# G431_Dev_V2.net
KiCad netlist of a schematic drawn in Altium Designer
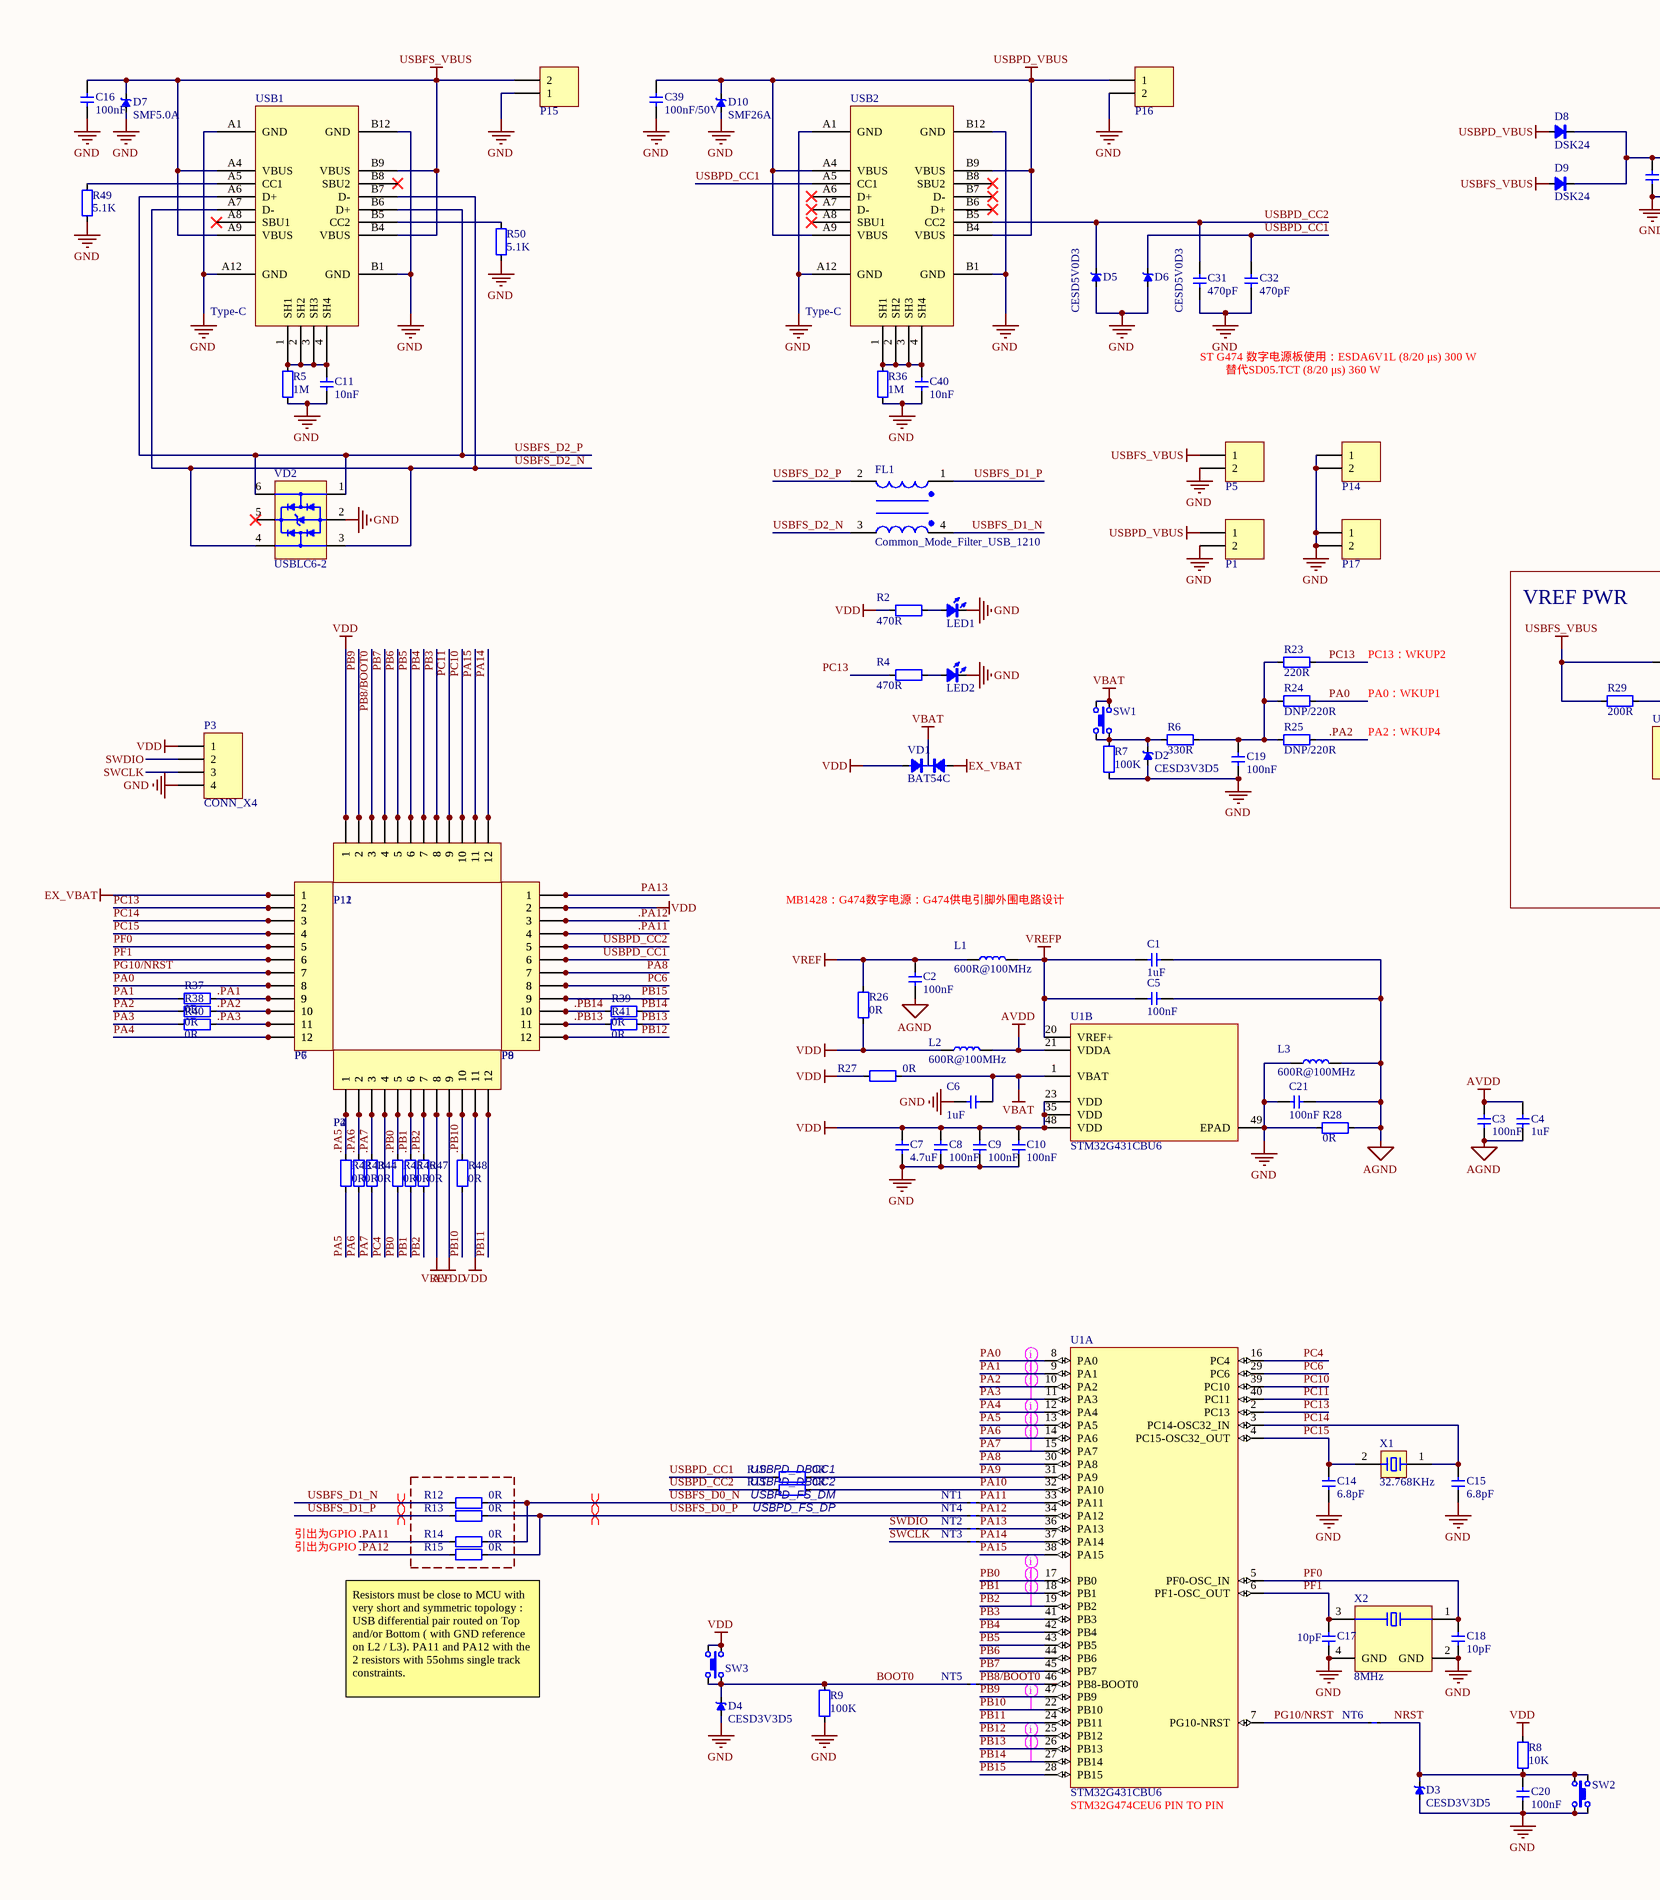
[diagram p0: G431_Dev_V2.SchDoc, left]
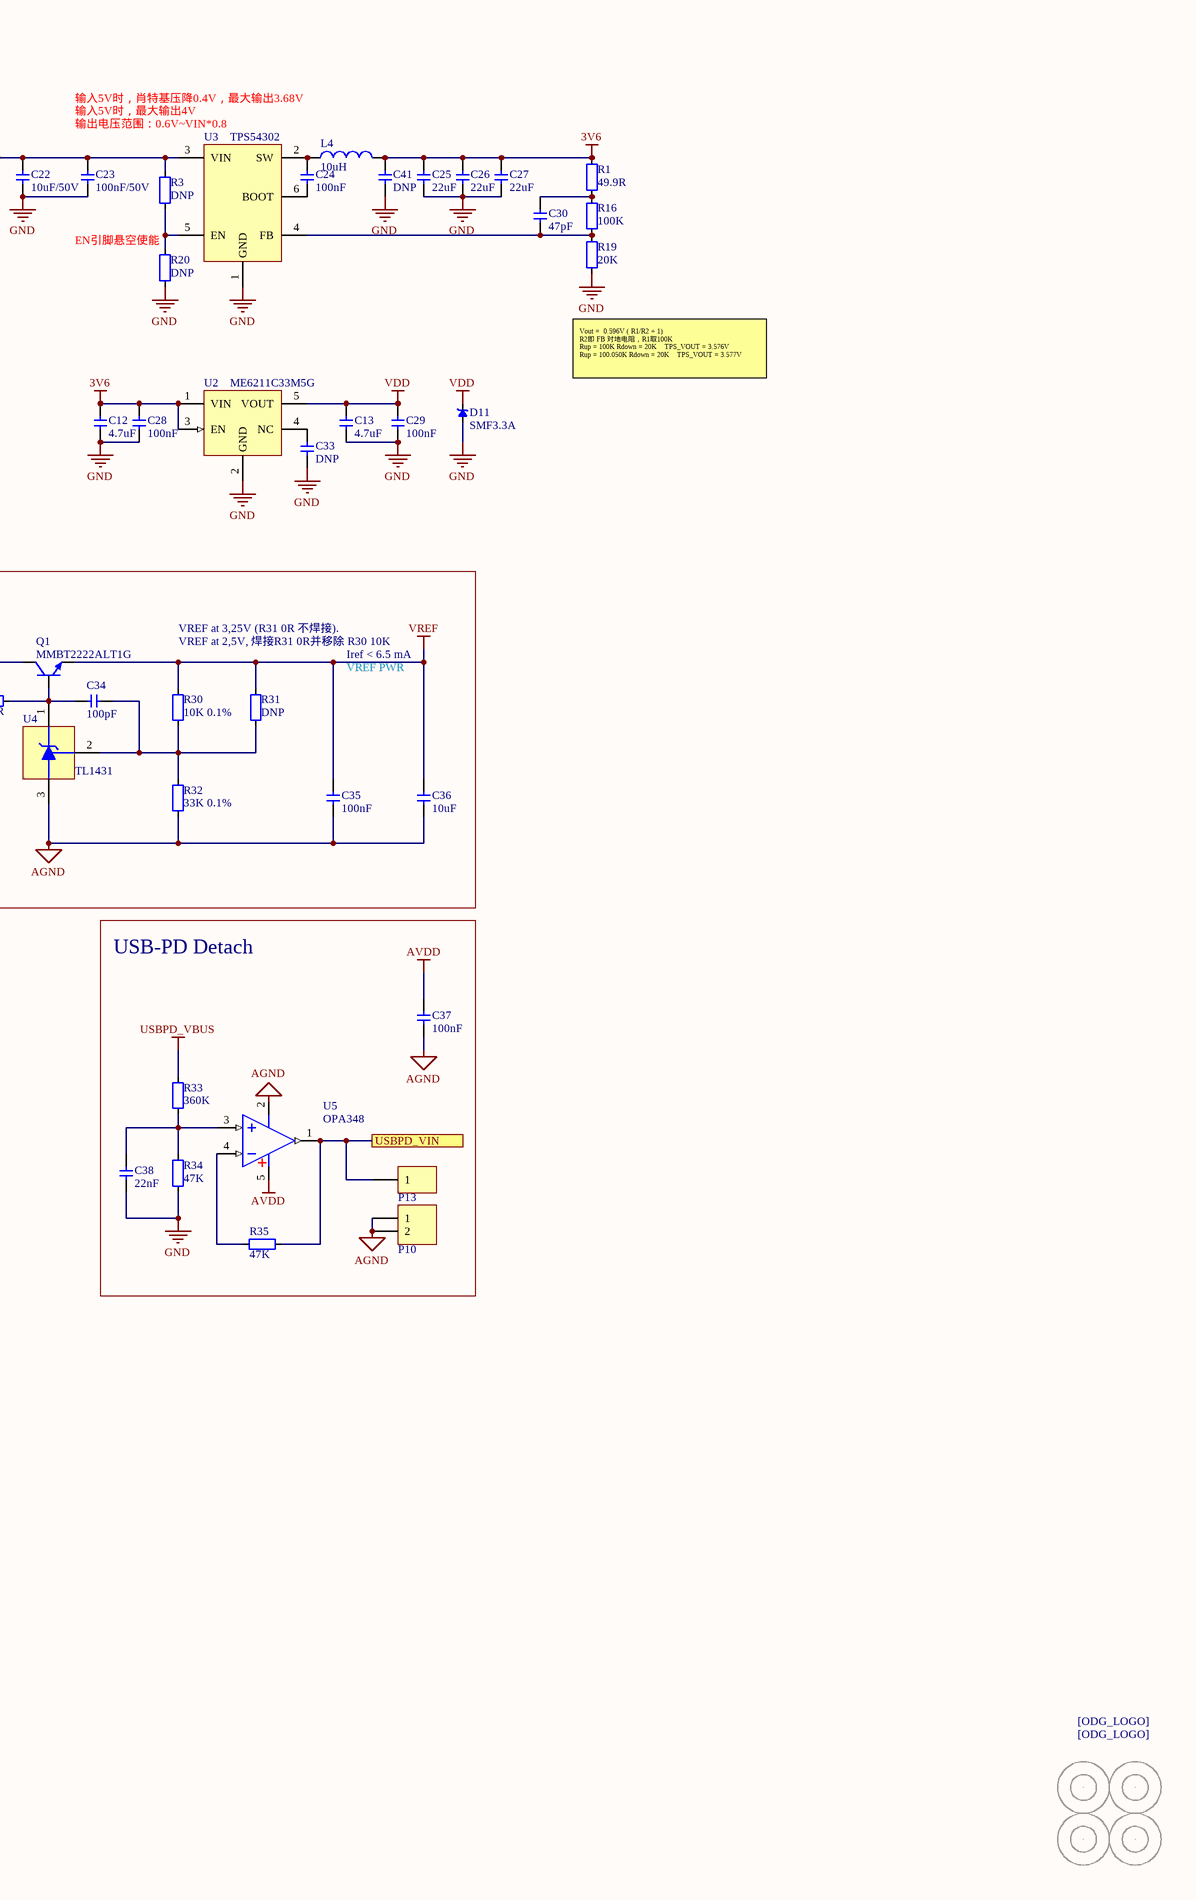
[diagram p1: G431_Dev_V2.SchDoc, right]

(export (version "E")
  (design (tool "Eeschema 10.0.6"))
  (components
    (comp (ref "*1")
      (value "ODG_LOGO")
      (footprint "ODG_LOGO")
      (libsource (lib "ODG_AD_Lib") (part "ODG_LOGO"))
    )
    (comp (ref "*2")
      (value "ODG_LOGO")
      (footprint "ODG_LOGO")
      (libsource (lib "ODG_AD_Lib") (part "ODG_LOGO"))
    )
    (comp (ref "C1")
      (value "1uF")
      (footprint "C0603")
      (description "Capacitor")
      (libsource (lib "ODG_AD_Lib") (part "CAP"))
    )
    (comp (ref "C2")
      (value "100nF")
      (footprint "C0402")
      (description "Capacitor")
      (libsource (lib "ODG_AD_Lib") (part "CAP"))
    )
    (comp (ref "C3")
      (value "100nF")
      (footprint "C0402")
      (description "Capacitor")
      (libsource (lib "ODG_AD_Lib") (part "CAP"))
    )
    (comp (ref "C4")
      (value "1uF")
      (footprint "C0603")
      (description "Capacitor")
      (libsource (lib "ODG_AD_Lib") (part "CAP"))
    )
    (comp (ref "C5")
      (value "100nF")
      (footprint "C0402")
      (description "Capacitor")
      (libsource (lib "ODG_AD_Lib") (part "CAP"))
    )
    (comp (ref "C6")
      (value "1uF")
      (footprint "C0603")
      (description "Capacitor")
      (libsource (lib "ODG_AD_Lib") (part "CAP"))
    )
    (comp (ref "C7")
      (value "4.7uF")
      (footprint "C0603")
      (description "Capacitor")
      (libsource (lib "ODG_AD_Lib") (part "CAP"))
    )
    (comp (ref "C8")
      (value "100nF")
      (footprint "C0402")
      (description "Capacitor")
      (libsource (lib "ODG_AD_Lib") (part "CAP"))
    )
    (comp (ref "C9")
      (value "100nF")
      (footprint "C0402")
      (description "Capacitor")
      (libsource (lib "ODG_AD_Lib") (part "CAP"))
    )
    (comp (ref "C10")
      (value "100nF")
      (footprint "C0402")
      (description "Capacitor")
      (libsource (lib "ODG_AD_Lib") (part "CAP"))
    )
    (comp (ref "C11")
      (value "10nF")
      (footprint "C0402")
      (description "Capacitor")
      (libsource (lib "ODG_AD_Lib") (part "CAP"))
    )
    (comp (ref "C12")
      (value "4.7uF")
      (footprint "C0603")
      (description "Capacitor")
      (libsource (lib "ODG_AD_Lib") (part "CAP"))
    )
    (comp (ref "C13")
      (value "4.7uF")
      (footprint "C0603")
      (description "Capacitor")
      (libsource (lib "ODG_AD_Lib") (part "CAP"))
    )
    (comp (ref "C14")
      (value "6.8pF")
      (footprint "C0402")
      (description "Capacitor")
      (libsource (lib "ODG_AD_Lib") (part "CAP"))
    )
    (comp (ref "C15")
      (value "6.8pF")
      (footprint "C0402")
      (description "Capacitor")
      (libsource (lib "ODG_AD_Lib") (part "CAP"))
    )
    (comp (ref "C16")
      (value "100nF")
      (footprint "C0402")
      (description "Capacitor")
      (libsource (lib "ODG_AD_Lib") (part "CAP"))
    )
    (comp (ref "C17")
      (value "10pF")
      (footprint "C0402")
      (description "Capacitor")
      (libsource (lib "ODG_AD_Lib") (part "CAP"))
    )
    (comp (ref "C18")
      (value "10pF")
      (footprint "C0402")
      (description "Capacitor")
      (libsource (lib "ODG_AD_Lib") (part "CAP"))
    )
    (comp (ref "C19")
      (value "100nF")
      (footprint "C0402")
      (description "Capacitor")
      (libsource (lib "ODG_AD_Lib") (part "CAP"))
    )
    (comp (ref "C20")
      (value "100nF")
      (footprint "C0402")
      (description "Capacitor")
      (libsource (lib "ODG_AD_Lib") (part "CAP"))
    )
    (comp (ref "C21")
      (value "100nF")
      (footprint "C0402")
      (description "Capacitor")
      (libsource (lib "ODG_AD_Lib") (part "CAP"))
    )
    (comp (ref "C22")
      (value "10uF/50V")
      (footprint "C1206")
      (description "Capacitor")
      (libsource (lib "ODG_AD_Lib") (part "CAP"))
    )
    (comp (ref "C23")
      (value "100nF/50V")
      (footprint "C0402")
      (description "Capacitor")
      (libsource (lib "ODG_AD_Lib") (part "CAP"))
    )
    (comp (ref "C24")
      (value "100nF")
      (footprint "C0402")
      (description "Capacitor")
      (libsource (lib "ODG_AD_Lib") (part "CAP"))
    )
    (comp (ref "C25")
      (value "22uF")
      (footprint "C0805")
      (description "Capacitor")
      (libsource (lib "ODG_AD_Lib") (part "CAP"))
    )
    (comp (ref "C26")
      (value "22uF")
      (footprint "C0805")
      (description "Capacitor")
      (libsource (lib "ODG_AD_Lib") (part "CAP"))
    )
    (comp (ref "C27")
      (value "22uF")
      (footprint "C0603")
      (description "Capacitor")
      (libsource (lib "ODG_AD_Lib") (part "CAP"))
    )
    (comp (ref "C28")
      (value "100nF")
      (footprint "C0402")
      (description "Capacitor")
      (libsource (lib "ODG_AD_Lib") (part "CAP"))
    )
    (comp (ref "C29")
      (value "100nF")
      (footprint "C0402")
      (description "Capacitor")
      (libsource (lib "ODG_AD_Lib") (part "CAP"))
    )
    (comp (ref "C30")
      (value "47pF")
      (footprint "C0402")
      (description "Capacitor")
      (libsource (lib "ODG_AD_Lib") (part "CAP"))
    )
    (comp (ref "C31")
      (value "470pF")
      (footprint "C0402")
      (description "Capacitor")
      (libsource (lib "ODG_AD_Lib") (part "CAP"))
    )
    (comp (ref "C32")
      (value "470pF")
      (footprint "C0402")
      (description "Capacitor")
      (libsource (lib "ODG_AD_Lib") (part "CAP"))
    )
    (comp (ref "C33")
      (value "DNP")
      (footprint "C0402")
      (description "Capacitor")
      (libsource (lib "ODG_AD_Lib") (part "CAP"))
    )
    (comp (ref "C34")
      (value "100pF")
      (footprint "C0402")
      (description "Capacitor")
      (libsource (lib "ODG_AD_Lib") (part "CAP"))
    )
    (comp (ref "C35")
      (value "100nF")
      (footprint "C0402")
      (description "Capacitor")
      (libsource (lib "ODG_AD_Lib") (part "CAP"))
    )
    (comp (ref "C36")
      (value "10uF")
      (footprint "C0603")
      (description "Capacitor")
      (libsource (lib "ODG_AD_Lib") (part "CAP"))
    )
    (comp (ref "C37")
      (value "100nF")
      (footprint "C0402")
      (description "Capacitor")
      (libsource (lib "ODG_AD_Lib") (part "CAP"))
    )
    (comp (ref "C38")
      (value "22nF")
      (footprint "C0402")
      (description "Capacitor")
      (libsource (lib "ODG_AD_Lib") (part "CAP"))
    )
    (comp (ref "C39")
      (value "100nF/50V")
      (footprint "C0402")
      (description "Capacitor")
      (libsource (lib "ODG_AD_Lib") (part "CAP"))
    )
    (comp (ref "C40")
      (value "10nF")
      (footprint "C0402")
      (description "Capacitor")
      (libsource (lib "ODG_AD_Lib") (part "CAP"))
    )
    (comp (ref "C41")
      (value "DNP")
      (footprint "C0805")
      (description "Capacitor")
      (libsource (lib "ODG_AD_Lib") (part "CAP"))
    )
    (comp (ref "D2")
      (value "CESD3V3D5")
      (footprint "SOD-523")
      (description "极性：Unidirectional")
      (fields
        (field (name "MF") "Taiwan Semiconductor Corporation")
        (field (name "DIGI-KEY_PART_NUMBER") "TESD5V0L1UCRJGTR-ND")
      )
      (libsource (lib "ODG_AD_Lib") (part "TVS_U"))
    )
    (comp (ref "D3")
      (value "CESD3V3D5")
      (footprint "SOD-523")
      (description "极性：Unidirectional")
      (fields
        (field (name "MF") "Taiwan Semiconductor Corporation")
        (field (name "DIGI-KEY_PART_NUMBER") "TESD5V0L1UCRJGTR-ND")
      )
      (libsource (lib "ODG_AD_Lib") (part "TVS_U"))
    )
    (comp (ref "D4")
      (value "CESD3V3D5")
      (footprint "SOD-523")
      (description "极性：Unidirectional")
      (fields
        (field (name "MF") "Taiwan Semiconductor Corporation")
        (field (name "DIGI-KEY_PART_NUMBER") "TESD5V0L1UCRJGTR-ND")
      )
      (libsource (lib "ODG_AD_Lib") (part "TVS_U"))
    )
    (comp (ref "D5")
      (value "CESD5V0D3")
      (footprint "SOD-323")
      (description "极性：Unidirectional")
      (fields
        (field (name "MF") "Taiwan Semiconductor Corporation")
        (field (name "DIGI-KEY_PART_NUMBER") "TESD5V0L1UCRJGTR-ND")
      )
      (libsource (lib "ODG_AD_Lib") (part "TVS_U"))
    )
    (comp (ref "D6")
      (value "CESD5V0D3")
      (footprint "SOD-323")
      (description "极性：Unidirectional")
      (fields
        (field (name "MF") "Taiwan Semiconductor Corporation")
        (field (name "DIGI-KEY_PART_NUMBER") "TESD5V0L1UCRJGTR-ND")
      )
      (libsource (lib "ODG_AD_Lib") (part "TVS_U"))
    )
    (comp (ref "D7")
      (value "SMF5.0A")
      (footprint "SOD123F")
      (description "极性：Unidirectional")
      (fields
        (field (name "MF") "Taiwan Semiconductor Corporation")
        (field (name "DIGI-KEY_PART_NUMBER") "TESD5V0L1UCRJGTR-ND")
      )
      (libsource (lib "ODG_AD_Lib") (part "TVS_U"))
    )
    (comp (ref "D8")
      (value "DSK24")
      (footprint "SOD123F")
      (description "二极管")
      (libsource (lib "ODG_AD_Lib") (part "DIODE"))
    )
    (comp (ref "D9")
      (value "DSK24")
      (footprint "SOD123F")
      (description "二极管")
      (libsource (lib "ODG_AD_Lib") (part "DIODE"))
    )
    (comp (ref "D10")
      (value "SMF26A")
      (footprint "SOD123F")
      (description "极性：Unidirectional")
      (fields
        (field (name "MF") "Taiwan Semiconductor Corporation")
        (field (name "DIGI-KEY_PART_NUMBER") "TESD5V0L1UCRJGTR-ND")
      )
      (libsource (lib "ODG_AD_Lib") (part "TVS_U"))
    )
    (comp (ref "D11")
      (value "SMF3.3A")
      (footprint "SOD123F")
      (description "极性：Unidirectional")
      (fields
        (field (name "MF") "Taiwan Semiconductor Corporation")
        (field (name "DIGI-KEY_PART_NUMBER") "TESD5V0L1UCRJGTR-ND")
      )
      (libsource (lib "ODG_AD_Lib") (part "TVS_U"))
    )
    (comp (ref "FL1")
      (value "Common_Mode_Filter_USB_1210")
      (footprint "FIL_1210_DLP11RB400UL2L")
      (description "Chip Common Mode Choke Coil")
      (fields (field (name "MP") "DLP11RB400UL2L"))
      (libsource (lib "ODG_AD_Lib") (part "Common_Mode_Filter_USB"))
    )
    (comp (ref "H1") (value "HOLE") (footprint "M2.1 D=4.2") (libsource (lib "ODG_AD_Lib") (part "HOLE")))
    (comp (ref "H2") (value "HOLE") (footprint "M2.1 D=4.2") (libsource (lib "ODG_AD_Lib") (part "HOLE")))
    (comp (ref "H3") (value "HOLE") (footprint "M2.1 D=4.2") (libsource (lib "ODG_AD_Lib") (part "HOLE")))
    (comp (ref "H4") (value "HOLE") (footprint "M2.1 D=4.2") (libsource (lib "ODG_AD_Lib") (part "HOLE")))
    (comp (ref "L1")
      (value "600R@100MHz")
      (footprint "FER0603")
      (description "贴片叠层电感")
      (libsource (lib "ODG_AD_Lib") (part "inductor_mini"))
    )
    (comp (ref "L2")
      (value "600R@100MHz")
      (footprint "FER0603")
      (description "贴片叠层电感")
      (libsource (lib "ODG_AD_Lib") (part "inductor_mini"))
    )
    (comp (ref "L3")
      (value "600R@100MHz")
      (footprint "FER0603")
      (description "贴片叠层电感")
      (libsource (lib "ODG_AD_Lib") (part "inductor_mini"))
    )
    (comp (ref "L4")
      (value "10uH")
      (footprint "INDUCTOR 0420 4.6X4.1X2MM")
      (description "功率电感")
      (libsource (lib "ODG_AD_Lib") (part "Inductor_power"))
    )
    (comp (ref "LED1") (value "LED") (footprint "LED0603_GREEN") (libsource (lib "ODG_AD_Lib") (part "LED")))
    (comp (ref "LED2") (value "LED") (footprint "LED0603_BLUE") (libsource (lib "ODG_AD_Lib") (part "LED")))
    (comp (ref "NT1")
      (value "NetTie")
      (footprint "NetTie_D=10MIL_C=10MIL")
      (description "Net Tie")
      (fields (field (name "PART NUMBER") "NetTie 0.2mm") (field (name "PUBLISHER") "Nordic Semiconductor"))
      (libsource (lib "ODG_AD_Lib") (part "NetTie"))
    )
    (comp (ref "NT2")
      (value "NetTie")
      (footprint "NetTie_D=10MIL_C=10MIL")
      (description "Net Tie")
      (fields (field (name "PART NUMBER") "NetTie 0.2mm") (field (name "PUBLISHER") "Nordic Semiconductor"))
      (libsource (lib "ODG_AD_Lib") (part "NetTie"))
    )
    (comp (ref "NT3")
      (value "NetTie")
      (footprint "NetTie_D=10MIL_C=10MIL")
      (description "Net Tie")
      (fields (field (name "PART NUMBER") "NetTie 0.2mm") (field (name "PUBLISHER") "Nordic Semiconductor"))
      (libsource (lib "ODG_AD_Lib") (part "NetTie"))
    )
    (comp (ref "NT4")
      (value "NetTie")
      (footprint "NetTie_D=10MIL_C=10MIL")
      (description "Net Tie")
      (fields (field (name "PART NUMBER") "NetTie 0.2mm") (field (name "PUBLISHER") "Nordic Semiconductor"))
      (libsource (lib "ODG_AD_Lib") (part "NetTie"))
    )
    (comp (ref "NT5")
      (value "NetTie")
      (footprint "NetTie_D=10MIL_C=10MIL")
      (description "Net Tie")
      (fields (field (name "PART NUMBER") "NetTie 0.2mm") (field (name "PUBLISHER") "Nordic Semiconductor"))
      (libsource (lib "ODG_AD_Lib") (part "NetTie"))
    )
    (comp (ref "NT6")
      (value "NetTie")
      (footprint "NetTie_D=10MIL_C=10MIL")
      (description "Net Tie")
      (fields (field (name "PART NUMBER") "NetTie 0.2mm") (field (name "PUBLISHER") "Nordic Semiconductor"))
      (libsource (lib "ODG_AD_Lib") (part "NetTie"))
    )
    (comp (ref "P1")
      (value "CONN_X2")
      (footprint "2.54mm_Male_x2")
      (libsource (lib "ODG_AD_Lib") (part "CONN_X2"))
    )
    (comp (ref "P2")
      (value "CONN_X12")
      (footprint "2.54MM_MALE_X12")
      (libsource (lib "") (part "CONN_X12_1"))
    )
    (comp (ref "P3")
      (value "CONN_X4")
      (footprint "2.54mm_Male_x4")
      (libsource (lib "ODG_AD_Lib") (part "CONN_X4"))
    )
    (comp (ref "P4")
      (value "CONN_X12")
      (footprint "2.54MM_MALE_X12")
      (libsource (lib "") (part "CONN_X12_1"))
    )
    (comp (ref "P5")
      (value "CONN_X2")
      (footprint "2.54mm_Male_x2")
      (libsource (lib "ODG_AD_Lib") (part "CONN_X2"))
    )
    (comp (ref "P6")
      (value "CONN_X12")
      (footprint "2.54MM_MALE_X12")
      (libsource (lib "") (part "CONN_X12_3"))
    )
    (comp (ref "P7")
      (value "CONN_X12")
      (footprint "2.54MM_MALE_X12")
      (libsource (lib "") (part "CONN_X12_3"))
    )
    (comp (ref "P8")
      (value "CONN_X12")
      (footprint "2.54MM_MALE_X12")
      (libsource (lib "ODG_AD_Lib") (part "CONN_X12"))
    )
    (comp (ref "P9")
      (value "CONN_X12")
      (footprint "2.54MM_MALE_X12")
      (libsource (lib "ODG_AD_Lib") (part "CONN_X12"))
    )
    (comp (ref "P10")
      (value "CONN_X2")
      (footprint "2.54mm_Male_x2")
      (libsource (lib "ODG_AD_Lib") (part "CONN_X2"))
    )
    (comp (ref "P11")
      (value "CONN_X12")
      (footprint "2.54MM_MALE_X12")
      (libsource (lib "") (part "CONN_X12_2"))
    )
    (comp (ref "P12")
      (value "CONN_X12")
      (footprint "2.54MM_MALE_X12")
      (libsource (lib "") (part "CONN_X12_2"))
    )
    (comp (ref "P13")
      (value "CONN_X1")
      (footprint "2.54mm_Male_x1")
      (libsource (lib "ODG_AD_Lib") (part "CONN_X1"))
    )
    (comp (ref "P14")
      (value "CONN_X2")
      (footprint "2.54mm_Male_x2")
      (libsource (lib "ODG_AD_Lib") (part "CONN_X2"))
    )
    (comp (ref "P15") (value "CONN_X2") (footprint "TE_1776275-2") (libsource (lib "") (part "CONN_X2_1")))
    (comp (ref "P16")
      (value "CONN_X2")
      (footprint "TE_1776275-2")
      (libsource (lib "ODG_AD_Lib") (part "CONN_X2"))
    )
    (comp (ref "P17")
      (value "CONN_X2")
      (footprint "2.54mm_Male_x2")
      (libsource (lib "ODG_AD_Lib") (part "CONN_X2"))
    )
    (comp (ref "Q1")
      (value "MMBT2222ALT1G")
      (footprint "INFINEON SOT-23-3")
      (description "NPN型")
      (libsource (lib "ODG_AD_Lib") (part "NPN"))
    )
    (comp (ref "R1")
      (value "49.9R")
      (footprint "R0402")
      (description "IEC Standard")
      (libsource (lib "") (part "RES_1"))
    )
    (comp (ref "R2")
      (value "470R")
      (footprint "R0402")
      (description "IEC Standard")
      (libsource (lib "ODG_AD_Lib") (part "RES"))
    )
    (comp (ref "R3")
      (value "DNP")
      (footprint "R0402")
      (description "IEC Standard")
      (libsource (lib "") (part "RES_3"))
    )
    (comp (ref "R4")
      (value "470R")
      (footprint "R0402")
      (description "IEC Standard")
      (libsource (lib "ODG_AD_Lib") (part "RES"))
    )
    (comp (ref "R5")
      (value "1M")
      (footprint "R0402")
      (description "IEC Standard")
      (libsource (lib "") (part "RES_2"))
    )
    (comp (ref "R6")
      (value "330R")
      (footprint "R0402")
      (description "IEC Standard")
      (libsource (lib "") (part "RES_3"))
    )
    (comp (ref "R7")
      (value "100K")
      (footprint "R0402")
      (description "IEC Standard")
      (libsource (lib "") (part "RES_1"))
    )
    (comp (ref "R8")
      (value "10K")
      (footprint "R0402")
      (description "IEC Standard")
      (libsource (lib "") (part "RES_1"))
    )
    (comp (ref "R9")
      (value "100K")
      (footprint "R0402")
      (description "IEC Standard")
      (libsource (lib "") (part "RES_1"))
    )
    (comp (ref "R10")
      (value "0R")
      (footprint "R0402")
      (description "IEC Standard")
      (libsource (lib "ODG_AD_Lib") (part "RES"))
    )
    (comp (ref "R11")
      (value "0R")
      (footprint "R0402")
      (description "IEC Standard")
      (libsource (lib "ODG_AD_Lib") (part "RES"))
    )
    (comp (ref "R12")
      (value "0R")
      (footprint "R0402")
      (description "IEC Standard")
      (libsource (lib "ODG_AD_Lib") (part "RES"))
    )
    (comp (ref "R13")
      (value "0R")
      (footprint "R0402")
      (description "IEC Standard")
      (libsource (lib "ODG_AD_Lib") (part "RES"))
    )
    (comp (ref "R14")
      (value "0R")
      (footprint "R0402")
      (description "IEC Standard")
      (libsource (lib "ODG_AD_Lib") (part "RES"))
    )
    (comp (ref "R15")
      (value "0R")
      (footprint "R0402")
      (description "IEC Standard")
      (libsource (lib "ODG_AD_Lib") (part "RES"))
    )
    (comp (ref "R16")
      (value "100K")
      (footprint "R0402")
      (description "IEC Standard")
      (libsource (lib "") (part "RES_1"))
    )
    (comp (ref "R19")
      (value "20K")
      (footprint "R0402")
      (description "IEC Standard")
      (libsource (lib "") (part "RES_1"))
    )
    (comp (ref "R20")
      (value "DNP")
      (footprint "R0402")
      (description "IEC Standard")
      (libsource (lib "") (part "RES_3"))
    )
    (comp (ref "R23")
      (value "220R")
      (footprint "R0402")
      (description "IEC Standard")
      (libsource (lib "") (part "RES_3"))
    )
    (comp (ref "R24")
      (value "DNP/220R")
      (footprint "R0402")
      (description "IEC Standard")
      (libsource (lib "") (part "RES_3"))
    )
    (comp (ref "R25")
      (value "DNP/220R")
      (footprint "R0402")
      (description "IEC Standard")
      (libsource (lib "") (part "RES_3"))
    )
    (comp (ref "R26")
      (value "0R")
      (footprint "R0402")
      (description "IEC Standard")
      (libsource (lib "") (part "RES_2"))
    )
    (comp (ref "R27")
      (value "0R")
      (footprint "R0402")
      (description "IEC Standard")
      (libsource (lib "ODG_AD_Lib") (part "RES"))
    )
    (comp (ref "R28")
      (value "0R")
      (footprint "R0402")
      (description "IEC Standard")
      (libsource (lib "") (part "RES_3"))
    )
    (comp (ref "R29")
      (value "200R")
      (footprint "R0402")
      (description "IEC Standard")
      (libsource (lib "") (part "RES_3"))
    )
    (comp (ref "R30")
      (value "10K 0.1%")
      (footprint "R0402")
      (description "IEC Standard")
      (libsource (lib "") (part "RES_2"))
    )
    (comp (ref "R31")
      (value "DNP")
      (footprint "R0402")
      (description "IEC Standard")
      (libsource (lib "") (part "RES_2"))
    )
    (comp (ref "R32")
      (value "33K 0.1%")
      (footprint "R0402")
      (description "IEC Standard")
      (libsource (lib "") (part "RES_2"))
    )
    (comp (ref "R33")
      (value "360K")
      (footprint "R0402")
      (description "IEC Standard")
      (libsource (lib "") (part "RES_2"))
    )
    (comp (ref "R34")
      (value "47K")
      (footprint "R0402")
      (description "IEC Standard")
      (libsource (lib "") (part "RES_1"))
    )
    (comp (ref "R35")
      (value "47K")
      (footprint "R0402")
      (description "IEC Standard")
      (libsource (lib "") (part "RES_3"))
    )
    (comp (ref "R36")
      (value "1M")
      (footprint "R0402")
      (description "IEC Standard")
      (libsource (lib "") (part "RES_2"))
    )
    (comp (ref "R37")
      (value "0R")
      (footprint "RES_TINY_0402")
      (description "IEC Standard")
      (libsource (lib "ODG_AD_Lib") (part "RES"))
    )
    (comp (ref "R38")
      (value "0R")
      (footprint "RES_TINY_0402")
      (description "IEC Standard")
      (libsource (lib "ODG_AD_Lib") (part "RES"))
    )
    (comp (ref "R39")
      (value "0R")
      (footprint "RES_TINY_0402")
      (description "IEC Standard")
      (libsource (lib "ODG_AD_Lib") (part "RES"))
    )
    (comp (ref "R40")
      (value "0R")
      (footprint "RES_TINY_0402")
      (description "IEC Standard")
      (libsource (lib "ODG_AD_Lib") (part "RES"))
    )
    (comp (ref "R41")
      (value "0R")
      (footprint "RES_TINY_0402")
      (description "IEC Standard")
      (libsource (lib "ODG_AD_Lib") (part "RES"))
    )
    (comp (ref "R42")
      (value "0R")
      (footprint "RES_TINY_0402")
      (description "IEC Standard")
      (libsource (lib "") (part "RES_1"))
    )
    (comp (ref "R43")
      (value "0R")
      (footprint "RES_TINY_0402")
      (description "IEC Standard")
      (libsource (lib "") (part "RES_1"))
    )
    (comp (ref "R44")
      (value "0R")
      (footprint "RES_TINY_0402")
      (description "IEC Standard")
      (libsource (lib "") (part "RES_1"))
    )
    (comp (ref "R45")
      (value "0R")
      (footprint "RES_TINY_0402")
      (description "IEC Standard")
      (libsource (lib "") (part "RES_1"))
    )
    (comp (ref "R46")
      (value "0R")
      (footprint "RES_TINY_0402")
      (description "IEC Standard")
      (libsource (lib "") (part "RES_1"))
    )
    (comp (ref "R47")
      (value "0R")
      (footprint "RES_TINY_0402")
      (description "IEC Standard")
      (libsource (lib "") (part "RES_1"))
    )
    (comp (ref "R48")
      (value "0R")
      (footprint "RES_TINY_0402")
      (description "IEC Standard")
      (libsource (lib "") (part "RES_1"))
    )
    (comp (ref "R49")
      (value "5.1K")
      (footprint "R0402")
      (description "IEC Standard")
      (libsource (lib "") (part "RES_2"))
    )
    (comp (ref "R50")
      (value "5.1K")
      (footprint "R0402")
      (description "IEC Standard")
      (libsource (lib "") (part "RES_1"))
    )
    (comp (ref "SW1")
      (value "Button-4P")
      (footprint "SWITCH_3X4X2.5_4PIN_SMD")
      (description "Button")
      (libsource (lib "ODG_AD_Lib") (part "Button-4P"))
    )
    (comp (ref "SW2")
      (value "Button-4P")
      (footprint "SWITCH_3X4X2.5_4PIN_SMD")
      (description "Button")
      (libsource (lib "ODG_AD_Lib") (part "Button-4P"))
    )
    (comp (ref "SW3")
      (value "Button-4P")
      (footprint "SWITCH_3X4X2.5_4PIN_SMD")
      (description "Button")
      (libsource (lib "ODG_AD_Lib") (part "Button-4P"))
    )
    (comp (ref "U1")
      (value "STM32G431CBU6")
      (footprint "UFQFPN-48_7X7X0P55MM")
      (fields (field (name "COPYRIGHT") "Copyright (C) 2023 Ultra Librarian. All rights reserved."))
      (libsource (lib "ODG_Project") (part "STM32G431CBU6"))
    )
    (comp (ref "U2")
      (value "ME6211C33M5G")
      (footprint "ANALOG TSOT-23-5 UJ-5")
      (description "线性稳压芯片")
      (libsource (lib "ODG_AD_Lib") (part "ME6211C33M5G"))
    )
    (comp (ref "U3")
      (value "TPS54302")
      (footprint "MICROCHIP SOT-23-6 M6")
      (description "4.5-V to 28-V Input, 3-A Output, EMI Friendly Synchronous Step Down Converter")
      (libsource (lib "ODG_Project") (part "TPS54302"))
    )
    (comp (ref "U4")
      (value "TL1431")
      (footprint "INFINEON SOT-23-3")
      (description "Programmable voltage reference")
      (libsource (lib "ODG_AD_Lib") (part "TL1431 (SOT23-3)"))
    )
    (comp (ref "U5")
      (value "OPA348")
      (footprint "ANALOG SOT-23-5 RJ-5")
      (description "精密、低噪声、CMOS、轨到轨输入/输出运算放大器")
      (libsource (lib "ODG_AD_Lib") (part "AD8605ARTZ"))
    )
    (comp (ref "USB1")
      (value "Type-C")
      (footprint "Type-C-TOP")
      (libsource (lib "ODG_AD_Lib") (part "USB-Type-C_16P"))
    )
    (comp (ref "USB2")
      (value "Type-C")
      (footprint "Type-C-TOP")
      (libsource (lib "ODG_AD_Lib") (part "USB-Type-C_16P"))
    )
    (comp (ref "VD1")
      (value "BAT54C")
      (footprint "INFINEON SOT-23-3")
      (description "贴片肖特基二极管")
      (libsource (lib "ODG_AD_Lib") (part "BAT54C"))
    )
    (comp (ref "VD2")
      (value "USBLC6-2")
      (footprint "MICROCHIP SOT-23-6 M6")
      (libsource (lib "ODG_AD_Lib") (part "USBLC6-2"))
    )
    (comp (ref "X1")
      (value "32.768KHz")
      (footprint "XTAL_2P_3215")
      (description "2脚无源石英晶振")
      (fields (field (name "版权归属") "源创客"))
      (libsource (lib "ODG_AD_Lib") (part "XTAL-2P"))
    )
    (comp (ref "X2")
      (value "8MHz")
      (footprint "EPSON TSX-3225")
      (description "4脚无源石英晶振")
      (fields (field (name "版权归属") "源创客"))
      (libsource (lib "ODG_AD_Lib") (part "XTAL-4P"))
    )
  )
  (nets
    (net (code "1") (name "/.PA1") (class "Default")
      (node (ref "P6") (pin "9") (pinfunction "9_9") (pintype "passive"))
      (node (ref "P7") (pin "9") (pinfunction "9_9") (pintype "passive"))
      (node (ref "R37") (pin "2") (pinfunction "2_2") (pintype "passive"))
    )
    (net (code "2") (name "/.PA2") (class "Default")
      (node (ref "P6") (pin "10") (pinfunction "10_10") (pintype "passive"))
      (node (ref "P7") (pin "10") (pinfunction "10_10") (pintype "passive"))
      (node (ref "R25") (pin "1") (pinfunction "1_1") (pintype "passive"))
      (node (ref "R38") (pin "2") (pinfunction "2_2") (pintype "passive"))
    )
    (net (code "3") (name "/.PA3") (class "Default")
      (node (ref "P6") (pin "11") (pinfunction "11_11") (pintype "passive"))
      (node (ref "P7") (pin "11") (pinfunction "11_11") (pintype "passive"))
      (node (ref "R40") (pin "2") (pinfunction "2_2") (pintype "passive"))
    )
    (net (code "4") (name "/.PA5") (class "Default")
      (node (ref "P2") (pin "1") (pinfunction "1_1") (pintype "passive"))
      (node (ref "P4") (pin "1") (pinfunction "1_1") (pintype "passive"))
      (node (ref "R42") (pin "1") (pinfunction "1_1") (pintype "passive"))
    )
    (net (code "5") (name "/.PA6") (class "Default")
      (node (ref "P2") (pin "2") (pinfunction "2_2") (pintype "passive"))
      (node (ref "P4") (pin "2") (pinfunction "2_2") (pintype "passive"))
      (node (ref "R43") (pin "1") (pinfunction "1_1") (pintype "passive"))
    )
    (net (code "6") (name "/.PA7") (class "Default")
      (node (ref "P2") (pin "3") (pinfunction "3_3") (pintype "passive"))
      (node (ref "P4") (pin "3") (pinfunction "3_3") (pintype "passive"))
      (node (ref "R44") (pin "1") (pinfunction "1_1") (pintype "passive"))
    )
    (net (code "7") (name "/.PA11") (class "Default")
      (node (ref "P8") (pin "4") (pinfunction "4_4") (pintype "passive"))
      (node (ref "P9") (pin "4") (pinfunction "4_4") (pintype "passive"))
      (node (ref "R14") (pin "1") (pinfunction "1_1") (pintype "passive"))
    )
    (net (code "8") (name "/.PA12") (class "Default")
      (node (ref "P8") (pin "3") (pinfunction "3_3") (pintype "passive"))
      (node (ref "P9") (pin "3") (pinfunction "3_3") (pintype "passive"))
      (node (ref "R15") (pin "1") (pinfunction "1_1") (pintype "passive"))
    )
    (net (code "9") (name "/.PB0") (class "Default")
      (node (ref "P2") (pin "5") (pinfunction "5_5") (pintype "passive"))
      (node (ref "P4") (pin "5") (pinfunction "5_5") (pintype "passive"))
      (node (ref "R45") (pin "1") (pinfunction "1_1") (pintype "passive"))
    )
    (net (code "10") (name "/.PB1") (class "Default")
      (node (ref "P2") (pin "6") (pinfunction "6_6") (pintype "passive"))
      (node (ref "P4") (pin "6") (pinfunction "6_6") (pintype "passive"))
      (node (ref "R46") (pin "1") (pinfunction "1_1") (pintype "passive"))
    )
    (net (code "11") (name "/.PB2") (class "Default")
      (node (ref "P2") (pin "7") (pinfunction "7_7") (pintype "passive"))
      (node (ref "P4") (pin "7") (pinfunction "7_7") (pintype "passive"))
      (node (ref "R47") (pin "1") (pinfunction "1_1") (pintype "passive"))
    )
    (net (code "12") (name "/.PB10") (class "Default")
      (node (ref "P2") (pin "10") (pinfunction "10_10") (pintype "passive"))
      (node (ref "P4") (pin "10") (pinfunction "10_10") (pintype "passive"))
      (node (ref "R48") (pin "1") (pinfunction "1_1") (pintype "passive"))
    )
    (net (code "13") (name "/.PB13") (class "Default")
      (node (ref "P8") (pin "11") (pinfunction "11_11") (pintype "passive"))
      (node (ref "P9") (pin "11") (pinfunction "11_11") (pintype "passive"))
      (node (ref "R41") (pin "1") (pinfunction "1_1") (pintype "passive"))
    )
    (net (code "14") (name "/.PB14") (class "Default")
      (node (ref "P8") (pin "10") (pinfunction "10_10") (pintype "passive"))
      (node (ref "P9") (pin "10") (pinfunction "10_10") (pintype "passive"))
      (node (ref "R39") (pin "1") (pinfunction "1_1") (pintype "passive"))
    )
    (net (code "15") (name "/BOOT0") (class "Default")
      (node (ref "D4") (pin "2") (pinfunction "2_2") (pintype "passive"))
      (node (ref "NT5") (pin "2") (pinfunction "2_2") (pintype "passive"))
      (node (ref "R9") (pin "1") (pinfunction "1_1") (pintype "passive"))
      (node (ref "SW3") (pin "1") (pinfunction "1_1") (pintype "passive"))
      (node (ref "SW3") (pin "2") (pinfunction "2_2") (pintype "passive"))
    )
    (net (code "16") (name "/NRST") (class "Default")
      (node (ref "C20") (pin "2") (pinfunction "2_2") (pintype "passive"))
      (node (ref "D3") (pin "2") (pinfunction "2_2") (pintype "passive"))
      (node (ref "NT6") (pin "1") (pinfunction "1_1") (pintype "passive"))
      (node (ref "R8") (pin "2") (pinfunction "2_2") (pintype "passive"))
      (node (ref "SW2") (pin "1") (pinfunction "1_1") (pintype "passive"))
      (node (ref "SW2") (pin "2") (pinfunction "2_2") (pintype "passive"))
    )
    (net (code "17") (name "/PA0") (class "Default")
      (node (ref "P6") (pin "8") (pinfunction "8_8") (pintype "passive"))
      (node (ref "P7") (pin "8") (pinfunction "8_8") (pintype "passive"))
      (node (ref "R24") (pin "1") (pinfunction "1_1") (pintype "passive"))
      (node (ref "U1") (pin "8") (pinfunction "PA0_8") (pintype "bidirectional"))
    )
    (net (code "18") (name "/PA1") (class "Default")
      (node (ref "R37") (pin "1") (pinfunction "1_1") (pintype "passive"))
      (node (ref "U1") (pin "9") (pinfunction "PA1_9") (pintype "bidirectional"))
    )
    (net (code "19") (name "/PA2") (class "Default")
      (node (ref "R38") (pin "1") (pinfunction "1_1") (pintype "passive"))
      (node (ref "U1") (pin "10") (pinfunction "PA2_10") (pintype "bidirectional"))
    )
    (net (code "20") (name "/PA3") (class "Default")
      (node (ref "R40") (pin "1") (pinfunction "1_1") (pintype "passive"))
      (node (ref "U1") (pin "11") (pinfunction "PA3_11") (pintype "bidirectional"))
    )
    (net (code "21") (name "/PA4") (class "Default")
      (node (ref "P6") (pin "12") (pinfunction "12_12") (pintype "passive"))
      (node (ref "P7") (pin "12") (pinfunction "12_12") (pintype "passive"))
      (node (ref "U1") (pin "12") (pinfunction "PA4_12") (pintype "bidirectional"))
    )
    (net (code "22") (name "/PA5") (class "Default")
      (node (ref "R42") (pin "2") (pinfunction "2_2") (pintype "passive"))
      (node (ref "U1") (pin "13") (pinfunction "PA5_13") (pintype "bidirectional"))
    )
    (net (code "23") (name "/PA6") (class "Default")
      (node (ref "R43") (pin "2") (pinfunction "2_2") (pintype "passive"))
      (node (ref "U1") (pin "14") (pinfunction "PA6_14") (pintype "bidirectional"))
    )
    (net (code "24") (name "/PA7") (class "Default")
      (node (ref "R44") (pin "2") (pinfunction "2_2") (pintype "passive"))
      (node (ref "U1") (pin "15") (pinfunction "PA7_15") (pintype "bidirectional"))
    )
    (net (code "25") (name "/PA8") (class "Default")
      (node (ref "P8") (pin "7") (pinfunction "7_7") (pintype "passive"))
      (node (ref "P9") (pin "7") (pinfunction "7_7") (pintype "passive"))
      (node (ref "U1") (pin "30") (pinfunction "PA8_30") (pintype "bidirectional"))
    )
    (net (code "26") (name "/PA9") (class "Default")
      (node (ref "R10") (pin "2") (pinfunction "2_2") (pintype "passive"))
      (node (ref "U1") (pin "31") (pinfunction "PA9_31") (pintype "bidirectional"))
    )
    (net (code "27") (name "/PA10") (class "Default")
      (node (ref "R11") (pin "2") (pinfunction "2_2") (pintype "passive"))
      (node (ref "U1") (pin "32") (pinfunction "PA10_32") (pintype "bidirectional"))
    )
    (net (code "28") (name "/PA11") (class "Default")
      (node (ref "NT1") (pin "1") (pinfunction "1_1") (pintype "passive"))
      (node (ref "U1") (pin "33") (pinfunction "PA11_33") (pintype "bidirectional"))
    )
    (net (code "29") (name "/PA12") (class "Default")
      (node (ref "NT4") (pin "1") (pinfunction "1_1") (pintype "passive"))
      (node (ref "U1") (pin "34") (pinfunction "PA12_34") (pintype "bidirectional"))
    )
    (net (code "30") (name "/PA13") (class "Default")
      (node (ref "NT2") (pin "1") (pinfunction "1_1") (pintype "passive"))
      (node (ref "P8") (pin "1") (pinfunction "1_1") (pintype "passive"))
      (node (ref "P9") (pin "1") (pinfunction "1_1") (pintype "passive"))
      (node (ref "U1") (pin "36") (pinfunction "PA13_36") (pintype "bidirectional"))
    )
    (net (code "31") (name "/PA14") (class "Default")
      (node (ref "NT3") (pin "1") (pinfunction "1_1") (pintype "passive"))
      (node (ref "P11") (pin "12") (pinfunction "12_12") (pintype "passive"))
      (node (ref "P12") (pin "12") (pinfunction "12_12") (pintype "passive"))
      (node (ref "U1") (pin "37") (pinfunction "PA14_37") (pintype "bidirectional"))
    )
    (net (code "32") (name "/PA15") (class "Default")
      (node (ref "P11") (pin "11") (pinfunction "11_11") (pintype "passive"))
      (node (ref "P12") (pin "11") (pinfunction "11_11") (pintype "passive"))
      (node (ref "U1") (pin "38") (pinfunction "PA15_38") (pintype "bidirectional"))
    )
    (net (code "33") (name "/PB0") (class "Default")
      (node (ref "R45") (pin "2") (pinfunction "2_2") (pintype "passive"))
      (node (ref "U1") (pin "17") (pinfunction "PB0_17") (pintype "bidirectional"))
    )
    (net (code "34") (name "/PB1") (class "Default")
      (node (ref "R46") (pin "2") (pinfunction "2_2") (pintype "passive"))
      (node (ref "U1") (pin "18") (pinfunction "PB1_18") (pintype "bidirectional"))
    )
    (net (code "35") (name "/PB2") (class "Default")
      (node (ref "R47") (pin "2") (pinfunction "2_2") (pintype "passive"))
      (node (ref "U1") (pin "19") (pinfunction "PB2_19") (pintype "bidirectional"))
    )
    (net (code "36") (name "/PB3") (class "Default")
      (node (ref "P11") (pin "8") (pinfunction "8_8") (pintype "passive"))
      (node (ref "P12") (pin "8") (pinfunction "8_8") (pintype "passive"))
      (node (ref "U1") (pin "41") (pinfunction "PB3_41") (pintype "bidirectional"))
    )
    (net (code "37") (name "/PB4") (class "Default")
      (node (ref "P11") (pin "7") (pinfunction "7_7") (pintype "passive"))
      (node (ref "P12") (pin "7") (pinfunction "7_7") (pintype "passive"))
      (node (ref "U1") (pin "42") (pinfunction "PB4_42") (pintype "bidirectional"))
    )
    (net (code "38") (name "/PB5") (class "Default")
      (node (ref "P11") (pin "6") (pinfunction "6_6") (pintype "passive"))
      (node (ref "P12") (pin "6") (pinfunction "6_6") (pintype "passive"))
      (node (ref "U1") (pin "43") (pinfunction "PB5_43") (pintype "bidirectional"))
    )
    (net (code "39") (name "/PB6") (class "Default")
      (node (ref "P11") (pin "5") (pinfunction "5_5") (pintype "passive"))
      (node (ref "P12") (pin "5") (pinfunction "5_5") (pintype "passive"))
      (node (ref "U1") (pin "44") (pinfunction "PB6_44") (pintype "bidirectional"))
    )
    (net (code "40") (name "/PB7") (class "Default")
      (node (ref "P11") (pin "4") (pinfunction "4_4") (pintype "passive"))
      (node (ref "P12") (pin "4") (pinfunction "4_4") (pintype "passive"))
      (node (ref "U1") (pin "45") (pinfunction "PB7_45") (pintype "bidirectional"))
    )
    (net (code "41") (name "/PB8{slash}BOOT0") (class "Default")
      (node (ref "NT5") (pin "1") (pinfunction "1_1") (pintype "passive"))
      (node (ref "P11") (pin "3") (pinfunction "3_3") (pintype "passive"))
      (node (ref "P12") (pin "3") (pinfunction "3_3") (pintype "passive"))
      (node (ref "U1") (pin "46") (pinfunction "PB8-BOOT0_46") (pintype "bidirectional"))
    )
    (net (code "42") (name "/PB9") (class "Default")
      (node (ref "P11") (pin "2") (pinfunction "2_2") (pintype "passive"))
      (node (ref "P12") (pin "2") (pinfunction "2_2") (pintype "passive"))
      (node (ref "U1") (pin "47") (pinfunction "PB9_47") (pintype "bidirectional"))
    )
    (net (code "43") (name "/PB10") (class "Default")
      (node (ref "R48") (pin "2") (pinfunction "2_2") (pintype "passive"))
      (node (ref "U1") (pin "22") (pinfunction "PB10_22") (pintype "bidirectional"))
    )
    (net (code "44") (name "/PB11") (class "Default")
      (node (ref "P2") (pin "12") (pinfunction "12_12") (pintype "passive"))
      (node (ref "P4") (pin "12") (pinfunction "12_12") (pintype "passive"))
      (node (ref "U1") (pin "24") (pinfunction "PB11_24") (pintype "bidirectional"))
    )
    (net (code "45") (name "/PB12") (class "Default")
      (node (ref "P8") (pin "12") (pinfunction "12_12") (pintype "passive"))
      (node (ref "P9") (pin "12") (pinfunction "12_12") (pintype "passive"))
      (node (ref "U1") (pin "25") (pinfunction "PB12_25") (pintype "bidirectional"))
    )
    (net (code "46") (name "/PB13") (class "Default")
      (node (ref "R41") (pin "2") (pinfunction "2_2") (pintype "passive"))
      (node (ref "U1") (pin "26") (pinfunction "PB13_26") (pintype "bidirectional"))
    )
    (net (code "47") (name "/PB14") (class "Default")
      (node (ref "R39") (pin "2") (pinfunction "2_2") (pintype "passive"))
      (node (ref "U1") (pin "27") (pinfunction "PB14_27") (pintype "bidirectional"))
    )
    (net (code "48") (name "/PB15") (class "Default")
      (node (ref "P8") (pin "9") (pinfunction "9_9") (pintype "passive"))
      (node (ref "P9") (pin "9") (pinfunction "9_9") (pintype "passive"))
      (node (ref "U1") (pin "28") (pinfunction "PB15_28") (pintype "bidirectional"))
    )
    (net (code "49") (name "/PC4") (class "Default")
      (node (ref "P2") (pin "4") (pinfunction "4_4") (pintype "passive"))
      (node (ref "P4") (pin "4") (pinfunction "4_4") (pintype "passive"))
      (node (ref "U1") (pin "16") (pinfunction "PC4_16") (pintype "bidirectional"))
    )
    (net (code "50") (name "/PC6") (class "Default")
      (node (ref "P8") (pin "8") (pinfunction "8_8") (pintype "passive"))
      (node (ref "P9") (pin "8") (pinfunction "8_8") (pintype "passive"))
      (node (ref "U1") (pin "29") (pinfunction "PC6_29") (pintype "bidirectional"))
    )
    (net (code "51") (name "/PC10") (class "Default")
      (node (ref "P11") (pin "10") (pinfunction "10_10") (pintype "passive"))
      (node (ref "P12") (pin "10") (pinfunction "10_10") (pintype "passive"))
      (node (ref "U1") (pin "39") (pinfunction "PC10_39") (pintype "bidirectional"))
    )
    (net (code "52") (name "/PC11") (class "Default")
      (node (ref "P11") (pin "9") (pinfunction "9_9") (pintype "passive"))
      (node (ref "P12") (pin "9") (pinfunction "9_9") (pintype "passive"))
      (node (ref "U1") (pin "40") (pinfunction "PC11_40") (pintype "bidirectional"))
    )
    (net (code "53") (name "/PC13") (class "Default")
      (node (ref "P6") (pin "2") (pinfunction "2_2") (pintype "passive"))
      (node (ref "P7") (pin "2") (pinfunction "2_2") (pintype "passive"))
      (node (ref "R23") (pin "1") (pinfunction "1_1") (pintype "passive"))
      (node (ref "R4") (pin "1") (pinfunction "1_1") (pintype "passive"))
      (node (ref "U1") (pin "2") (pinfunction "PC13_2") (pintype "bidirectional"))
    )
    (net (code "54") (name "/PC14") (class "Default")
      (node (ref "C15") (pin "1") (pinfunction "1_1") (pintype "passive"))
      (node (ref "P6") (pin "3") (pinfunction "3_3") (pintype "passive"))
      (node (ref "P7") (pin "3") (pinfunction "3_3") (pintype "passive"))
      (node (ref "U1") (pin "3") (pinfunction "PC14-OSC32_IN_3") (pintype "bidirectional"))
      (node (ref "X1") (pin "1") (pinfunction "1_1") (pintype "passive"))
    )
    (net (code "55") (name "/PC15") (class "Default")
      (node (ref "C14") (pin "1") (pinfunction "1_1") (pintype "passive"))
      (node (ref "P6") (pin "4") (pinfunction "4_4") (pintype "passive"))
      (node (ref "P7") (pin "4") (pinfunction "4_4") (pintype "passive"))
      (node (ref "U1") (pin "4") (pinfunction "PC15-OSC32_OUT_4") (pintype "bidirectional"))
      (node (ref "X1") (pin "2") (pinfunction "2_2") (pintype "passive"))
    )
    (net (code "56") (name "/PF0") (class "Default")
      (node (ref "C18") (pin "1") (pinfunction "1_1") (pintype "passive"))
      (node (ref "P6") (pin "5") (pinfunction "5_5") (pintype "passive"))
      (node (ref "P7") (pin "5") (pinfunction "5_5") (pintype "passive"))
      (node (ref "U1") (pin "5") (pinfunction "PF0-OSC_IN_5") (pintype "bidirectional"))
      (node (ref "X2") (pin "1") (pinfunction "1_1") (pintype "passive"))
    )
    (net (code "57") (name "/PF1") (class "Default")
      (node (ref "C17") (pin "1") (pinfunction "1_1") (pintype "passive"))
      (node (ref "P6") (pin "6") (pinfunction "6_6") (pintype "passive"))
      (node (ref "P7") (pin "6") (pinfunction "6_6") (pintype "passive"))
      (node (ref "U1") (pin "6") (pinfunction "PF1-OSC_OUT_6") (pintype "bidirectional"))
      (node (ref "X2") (pin "3") (pinfunction "3_3") (pintype "passive"))
    )
    (net (code "58") (name "/PG10{slash}NRST") (class "Default")
      (node (ref "NT6") (pin "2") (pinfunction "2_2") (pintype "passive"))
      (node (ref "P6") (pin "7") (pinfunction "7_7") (pintype "passive"))
      (node (ref "P7") (pin "7") (pinfunction "7_7") (pintype "passive"))
      (node (ref "U1") (pin "7") (pinfunction "PG10-NRST_7") (pintype "bidirectional"))
    )
    (net (code "59") (name "/SWCLK") (class "Default")
      (node (ref "NT3") (pin "2") (pinfunction "2_2") (pintype "passive"))
      (node (ref "P3") (pin "3") (pinfunction "3_3") (pintype "passive"))
    )
    (net (code "60") (name "/SWDIO") (class "Default")
      (node (ref "NT2") (pin "2") (pinfunction "2_2") (pintype "passive"))
      (node (ref "P3") (pin "2") (pinfunction "2_2") (pintype "passive"))
    )
    (net (code "61") (name "/USBFS_D0_N") (class "Default")
      (node (ref "NT1") (pin "2") (pinfunction "2_2") (pintype "passive"))
      (node (ref "R12") (pin "2") (pinfunction "2_2") (pintype "passive"))
      (node (ref "R14") (pin "2") (pinfunction "2_2") (pintype "passive"))
    )
    (net (code "62") (name "/USBFS_D0_P") (class "Default")
      (node (ref "NT4") (pin "2") (pinfunction "2_2") (pintype "passive"))
      (node (ref "R13") (pin "2") (pinfunction "2_2") (pintype "passive"))
      (node (ref "R15") (pin "2") (pinfunction "2_2") (pintype "passive"))
    )
    (net (code "63") (name "/USBFS_D1_N") (class "Default")
      (node (ref "FL1") (pin "4") (pinfunction "4_4") (pintype "passive"))
      (node (ref "R12") (pin "1") (pinfunction "1_1") (pintype "passive"))
    )
    (net (code "64") (name "/USBFS_D1_P") (class "Default")
      (node (ref "FL1") (pin "1") (pinfunction "1_1") (pintype "passive"))
      (node (ref "R13") (pin "1") (pinfunction "1_1") (pintype "passive"))
    )
    (net (code "65") (name "/USBFS_D2_N") (class "Default")
      (node (ref "FL1") (pin "3") (pinfunction "3_3") (pintype "passive"))
      (node (ref "USB1") (pin "A7") (pinfunction "D-_A7") (pintype "passive"))
      (node (ref "USB1") (pin "B7") (pinfunction "D-_B7") (pintype "passive"))
      (node (ref "VD2") (pin "3") (pinfunction "I/O2_3") (pintype "passive"))
      (node (ref "VD2") (pin "4") (pinfunction "I/O2_4") (pintype "passive"))
    )
    (net (code "66") (name "/USBFS_D2_P") (class "Default")
      (node (ref "FL1") (pin "2") (pinfunction "2_2") (pintype "passive"))
      (node (ref "USB1") (pin "A6") (pinfunction "D+_A6") (pintype "passive"))
      (node (ref "USB1") (pin "B6") (pinfunction "D+_B6") (pintype "passive"))
      (node (ref "VD2") (pin "1") (pinfunction "I/O1_1") (pintype "passive"))
      (node (ref "VD2") (pin "6") (pinfunction "I/O1_6") (pintype "passive"))
    )
    (net (code "67") (name "/USBPD_CC1") (class "Default")
      (node (ref "C32") (pin "1") (pinfunction "1_1") (pintype "passive"))
      (node (ref "D6") (pin "2") (pinfunction "2_2") (pintype "passive"))
      (node (ref "P8") (pin "6") (pinfunction "6_6") (pintype "passive"))
      (node (ref "P9") (pin "6") (pinfunction "6_6") (pintype "passive"))
      (node (ref "R10") (pin "1") (pinfunction "1_1") (pintype "passive"))
      (node (ref "USB2") (pin "A5") (pinfunction "CC1_A5") (pintype "passive"))
    )
    (net (code "68") (name "/USBPD_CC2") (class "Default")
      (node (ref "C31") (pin "2") (pinfunction "2_2") (pintype "passive"))
      (node (ref "D5") (pin "2") (pinfunction "2_2") (pintype "passive"))
      (node (ref "P8") (pin "5") (pinfunction "5_5") (pintype "passive"))
      (node (ref "P9") (pin "5") (pinfunction "5_5") (pintype "passive"))
      (node (ref "R11") (pin "1") (pinfunction "1_1") (pintype "passive"))
      (node (ref "USB2") (pin "B5") (pinfunction "CC2_B5") (pintype "passive"))
    )
    (net (code "69") (name "/USBPD_VIN") (class "Default")
      (node (ref "P13") (pin "1") (pinfunction "1_1") (pintype "passive"))
      (node (ref "R35") (pin "1") (pinfunction "1_1") (pintype "passive"))
      (node (ref "U5") (pin "1") (pinfunction "OUT_1") (pintype "output"))
    )
    (net (code "70") (name "3V6") (class "Default")
      (node (ref "C12") (pin "2") (pinfunction "2_2") (pintype "passive"))
      (node (ref "C25") (pin "1") (pinfunction "1_1") (pintype "passive"))
      (node (ref "C26") (pin "1") (pinfunction "1_1") (pintype "passive"))
      (node (ref "C27") (pin "1") (pinfunction "1_1") (pintype "passive"))
      (node (ref "C28") (pin "1") (pinfunction "1_1") (pintype "passive"))
      (node (ref "C41") (pin "2") (pinfunction "2_2") (pintype "passive"))
      (node (ref "L4") (pin "2") (pinfunction "2_2") (pintype "passive"))
      (node (ref "R1") (pin "1") (pinfunction "1_1") (pintype "passive"))
      (node (ref "U2") (pin "1") (pinfunction "VIN_1") (pintype "passive"))
      (node (ref "U2") (pin "3") (pinfunction "EN_3") (pintype "input"))
    )
    (net (code "71") (name "AGND") (class "Default")
      (node (ref "C1") (pin "2") (pinfunction "2_2") (pintype "passive"))
      (node (ref "C2") (pin "1") (pinfunction "1_1") (pintype "passive"))
      (node (ref "C21") (pin "1") (pinfunction "1_1") (pintype "passive"))
      (node (ref "C3") (pin "1") (pinfunction "1_1") (pintype "passive"))
      (node (ref "C35") (pin "2") (pinfunction "2_2") (pintype "passive"))
      (node (ref "C36") (pin "2") (pinfunction "2_2") (pintype "passive"))
      (node (ref "C37") (pin "2") (pinfunction "2_2") (pintype "passive"))
      (node (ref "C4") (pin "1") (pinfunction "1_1") (pintype "passive"))
      (node (ref "C5") (pin "2") (pinfunction "2_2") (pintype "passive"))
      (node (ref "L3") (pin "2") (pinfunction "2_2") (pintype "passive"))
      (node (ref "P10") (pin "1") (pinfunction "1_1") (pintype "passive"))
      (node (ref "P10") (pin "2") (pinfunction "2_2") (pintype "passive"))
      (node (ref "R28") (pin "1") (pinfunction "1_1") (pintype "passive"))
      (node (ref "R32") (pin "1") (pinfunction "1_1") (pintype "passive"))
      (node (ref "U4") (pin "3") (pinfunction "Anode_3") (pintype "passive"))
      (node (ref "U5") (pin "2") (pinfunction "V-_2") (pintype "power_in"))
    )
    (net (code "72") (name "AVDD") (class "Default")
      (node (ref "C3") (pin "2") (pinfunction "2_2") (pintype "passive"))
      (node (ref "C37") (pin "1") (pinfunction "1_1") (pintype "passive"))
      (node (ref "C4") (pin "2") (pinfunction "2_2") (pintype "passive"))
      (node (ref "L2") (pin "2") (pinfunction "2_2") (pintype "passive"))
      (node (ref "P2") (pin "9") (pinfunction "9_9") (pintype "passive"))
      (node (ref "P4") (pin "9") (pinfunction "9_9") (pintype "passive"))
      (node (ref "U1") (pin "21") (pinfunction "VDDA_21") (pintype "power_in"))
      (node (ref "U5") (pin "5") (pinfunction "V+_5") (pintype "power_in"))
    )
    (net (code "73") (name "EX_VBAT") (class "Default")
      (node (ref "P6") (pin "1") (pinfunction "1_1") (pintype "passive"))
      (node (ref "P7") (pin "1") (pinfunction "1_1") (pintype "passive"))
      (node (ref "VD1") (pin "2") (pinfunction "2_2") (pintype "passive"))
    )
    (net (code "74") (name "GND") (class "Default")
      (node (ref "C10") (pin "1") (pinfunction "1_1") (pintype "passive"))
      (node (ref "C11") (pin "1") (pinfunction "1_1") (pintype "passive"))
      (node (ref "C12") (pin "1") (pinfunction "1_1") (pintype "passive"))
      (node (ref "C13") (pin "1") (pinfunction "1_1") (pintype "passive"))
      (node (ref "C14") (pin "2") (pinfunction "2_2") (pintype "passive"))
      (node (ref "C15") (pin "2") (pinfunction "2_2") (pintype "passive"))
      (node (ref "C16") (pin "2") (pinfunction "2_2") (pintype "passive"))
      (node (ref "C17") (pin "2") (pinfunction "2_2") (pintype "passive"))
      (node (ref "C18") (pin "2") (pinfunction "2_2") (pintype "passive"))
      (node (ref "C19") (pin "1") (pinfunction "1_1") (pintype "passive"))
      (node (ref "C20") (pin "1") (pinfunction "1_1") (pintype "passive"))
      (node (ref "C21") (pin "2") (pinfunction "2_2") (pintype "passive"))
      (node (ref "C22") (pin "2") (pinfunction "2_2") (pintype "passive"))
      (node (ref "C23") (pin "2") (pinfunction "2_2") (pintype "passive"))
      (node (ref "C25") (pin "2") (pinfunction "2_2") (pintype "passive"))
      (node (ref "C26") (pin "2") (pinfunction "2_2") (pintype "passive"))
      (node (ref "C27") (pin "2") (pinfunction "2_2") (pintype "passive"))
      (node (ref "C28") (pin "2") (pinfunction "2_2") (pintype "passive"))
      (node (ref "C29") (pin "2") (pinfunction "2_2") (pintype "passive"))
      (node (ref "C31") (pin "1") (pinfunction "1_1") (pintype "passive"))
      (node (ref "C32") (pin "2") (pinfunction "2_2") (pintype "passive"))
      (node (ref "C33") (pin "2") (pinfunction "2_2") (pintype "passive"))
      (node (ref "C38") (pin "2") (pinfunction "2_2") (pintype "passive"))
      (node (ref "C39") (pin "2") (pinfunction "2_2") (pintype "passive"))
      (node (ref "C40") (pin "1") (pinfunction "1_1") (pintype "passive"))
      (node (ref "C41") (pin "1") (pinfunction "1_1") (pintype "passive"))
      (node (ref "C6") (pin "1") (pinfunction "1_1") (pintype "passive"))
      (node (ref "C7") (pin "1") (pinfunction "1_1") (pintype "passive"))
      (node (ref "C8") (pin "1") (pinfunction "1_1") (pintype "passive"))
      (node (ref "C9") (pin "1") (pinfunction "1_1") (pintype "passive"))
      (node (ref "D10") (pin "1") (pinfunction "1_1") (pintype "passive"))
      (node (ref "D11") (pin "1") (pinfunction "1_1") (pintype "passive"))
      (node (ref "D2") (pin "1") (pinfunction "1_1") (pintype "passive"))
      (node (ref "D3") (pin "1") (pinfunction "1_1") (pintype "passive"))
      (node (ref "D4") (pin "1") (pinfunction "1_1") (pintype "passive"))
      (node (ref "D5") (pin "1") (pinfunction "1_1") (pintype "passive"))
      (node (ref "D6") (pin "1") (pinfunction "1_1") (pintype "passive"))
      (node (ref "D7") (pin "1") (pinfunction "1_1") (pintype "passive"))
      (node (ref "L3") (pin "1") (pintype "passive"))
      (node (ref "LED1") (pin "2") (pinfunction "K_2") (pintype "passive"))
      (node (ref "LED2") (pin "2") (pinfunction "K_2") (pintype "passive"))
      (node (ref "P1") (pin "2") (pinfunction "2_2") (pintype "passive"))
      (node (ref "P14") (pin "1") (pinfunction "1_1") (pintype "passive"))
      (node (ref "P14") (pin "2") (pinfunction "2_2") (pintype "passive"))
      (node (ref "P15") (pin "1") (pinfunction "1_1") (pintype "passive"))
      (node (ref "P16") (pin "2") (pinfunction "2_2") (pintype "passive"))
      (node (ref "P17") (pin "1") (pinfunction "1_1") (pintype "passive"))
      (node (ref "P17") (pin "2") (pinfunction "2_2") (pintype "passive"))
      (node (ref "P3") (pin "4") (pinfunction "4_4") (pintype "passive"))
      (node (ref "P5") (pin "2") (pinfunction "2_2") (pintype "passive"))
      (node (ref "R19") (pin "2") (pinfunction "2_2") (pintype "passive"))
      (node (ref "R20") (pin "2") (pinfunction "2_2") (pintype "passive"))
      (node (ref "R28") (pin "2") (pinfunction "2_2") (pintype "passive"))
      (node (ref "R34") (pin "2") (pinfunction "2_2") (pintype "passive"))
      (node (ref "R36") (pin "1") (pinfunction "1_1") (pintype "passive"))
      (node (ref "R49") (pin "1") (pinfunction "1_1") (pintype "passive"))
      (node (ref "R5") (pin "1") (pinfunction "1_1") (pintype "passive"))
      (node (ref "R50") (pin "2") (pinfunction "2_2") (pintype "passive"))
      (node (ref "R7") (pin "2") (pinfunction "2_2") (pintype "passive"))
      (node (ref "R9") (pin "2") (pinfunction "2_2") (pintype "passive"))
      (node (ref "SW2") (pin "3") (pinfunction "3_3") (pintype "passive"))
      (node (ref "SW2") (pin "4") (pinfunction "4_4") (pintype "passive"))
      (node (ref "U1") (pin "49") (pinfunction "EPAD_49") (pintype "passive"))
      (node (ref "U2") (pin "2") (pinfunction "GND_2") (pintype "passive"))
      (node (ref "U3") (pin "1") (pinfunction "GND_1") (pintype "passive"))
      (node (ref "USB1") (pin "A1") (pinfunction "GND_A1") (pintype "passive"))
      (node (ref "USB1") (pin "A12") (pinfunction "GND_A12") (pintype "passive"))
      (node (ref "USB1") (pin "B1") (pinfunction "GND_B1") (pintype "passive"))
      (node (ref "USB1") (pin "B12") (pinfunction "GND_B12") (pintype "passive"))
      (node (ref "USB2") (pin "A1") (pinfunction "GND_A1") (pintype "passive"))
      (node (ref "USB2") (pin "A12") (pinfunction "GND_A12") (pintype "passive"))
      (node (ref "USB2") (pin "B1") (pinfunction "GND_B1") (pintype "passive"))
      (node (ref "USB2") (pin "B12") (pinfunction "GND_B12") (pintype "passive"))
      (node (ref "VD2") (pin "2") (pinfunction "GND_2") (pintype "passive"))
      (node (ref "X2") (pin "2") (pinfunction "GND_2") (pintype "passive"))
      (node (ref "X2") (pin "4") (pinfunction "GND_4") (pintype "passive"))
    )
    (net (code "75") (name "Net-(C19-Pad2)") (class "Default")
      (node (ref "C19") (pin "2") (pinfunction "2_2") (pintype "passive"))
      (node (ref "R23") (pin "2") (pinfunction "2_2") (pintype "passive"))
      (node (ref "R24") (pin "2") (pinfunction "2_2") (pintype "passive"))
      (node (ref "R25") (pin "2") (pinfunction "2_2") (pintype "passive"))
      (node (ref "R6") (pin "1") (pinfunction "1_1") (pintype "passive"))
    )
    (net (code "76") (name "Net-(C30-Pad1)") (class "Default")
      (node (ref "C30") (pin "1") (pinfunction "1_1") (pintype "passive"))
      (node (ref "R1") (pin "2") (pinfunction "2_2") (pintype "passive"))
      (node (ref "R16") (pin "1") (pinfunction "1_1") (pintype "passive"))
    )
    (net (code "77") (name "Net-(D2-Pad2)") (class "Default")
      (node (ref "D2") (pin "2") (pinfunction "2_2") (pintype "passive"))
      (node (ref "R6") (pin "2") (pinfunction "2_2") (pintype "passive"))
      (node (ref "R7") (pin "1") (pinfunction "1_1") (pintype "passive"))
      (node (ref "SW1") (pin "1") (pinfunction "1_1") (pintype "passive"))
      (node (ref "SW1") (pin "2") (pinfunction "2_2") (pintype "passive"))
    )
    (net (code "78") (name "Net-(D8-C)") (class "Default")
      (node (ref "C22") (pin "1") (pinfunction "1_1") (pintype "passive"))
      (node (ref "C23") (pin "1") (pinfunction "1_1") (pintype "passive"))
      (node (ref "D8") (pin "2") (pinfunction "C_2") (pintype "passive"))
      (node (ref "D9") (pin "2") (pinfunction "C_2") (pintype "passive"))
      (node (ref "R3") (pin "1") (pinfunction "1_1") (pintype "passive"))
      (node (ref "U3") (pin "3") (pinfunction "VIN_3") (pintype "passive"))
    )
    (net (code "79") (name "Net-(LED1-A)") (class "Default")
      (node (ref "LED1") (pin "1") (pinfunction "A_1") (pintype "passive"))
      (node (ref "R2") (pin "2") (pinfunction "2_2") (pintype "passive"))
    )
    (net (code "80") (name "Net-(LED2-A)") (class "Default")
      (node (ref "LED2") (pin "1") (pinfunction "A_1") (pintype "passive"))
      (node (ref "R4") (pin "2") (pinfunction "2_2") (pintype "passive"))
    )
    (net (code "81") (name "Net-(Q1-B)") (class "Default")
      (node (ref "C34") (pin "2") (pinfunction "2_2") (pintype "passive"))
      (node (ref "Q1") (pin "1") (pinfunction "B_1") (pintype "passive"))
      (node (ref "R29") (pin "1") (pinfunction "1_1") (pintype "passive"))
      (node (ref "U4") (pin "1") (pinfunction "Cathode_1") (pintype "passive"))
    )
    (net (code "82") (name "Net-(U2-NC)") (class "Default")
      (node (ref "C33") (pin "1") (pinfunction "1_1") (pintype "passive"))
      (node (ref "U2") (pin "4") (pinfunction "NC_4") (pintype "passive"))
    )
    (net (code "83") (name "Net-(U3-BOOT)") (class "Default")
      (node (ref "C24") (pin "1") (pinfunction "1_1") (pintype "passive"))
      (node (ref "U3") (pin "6") (pinfunction "BOOT_6") (pintype "passive"))
    )
    (net (code "84") (name "Net-(U3-EN)") (class "Default")
      (node (ref "R20") (pin "1") (pinfunction "1_1") (pintype "passive"))
      (node (ref "R3") (pin "2") (pinfunction "2_2") (pintype "passive"))
      (node (ref "U3") (pin "5") (pinfunction "EN_5") (pintype "passive"))
    )
    (net (code "85") (name "Net-(U3-FB)") (class "Default")
      (node (ref "C30") (pin "2") (pinfunction "2_2") (pintype "passive"))
      (node (ref "R16") (pin "2") (pinfunction "2_2") (pintype "passive"))
      (node (ref "R19") (pin "1") (pinfunction "1_1") (pintype "passive"))
      (node (ref "U3") (pin "4") (pinfunction "FB_4") (pintype "passive"))
    )
    (net (code "86") (name "Net-(U3-SW)") (class "Default")
      (node (ref "C24") (pin "2") (pinfunction "2_2") (pintype "passive"))
      (node (ref "L4") (pin "1") (pintype "passive"))
      (node (ref "U3") (pin "2") (pinfunction "SW_2") (pintype "passive"))
    )
    (net (code "87") (name "Net-(U4-Ref)") (class "Default")
      (node (ref "C34") (pin "1") (pinfunction "1_1") (pintype "passive"))
      (node (ref "R30") (pin "1") (pinfunction "1_1") (pintype "passive"))
      (node (ref "R31") (pin "1") (pinfunction "1_1") (pintype "passive"))
      (node (ref "R32") (pin "2") (pinfunction "2_2") (pintype "passive"))
      (node (ref "U4") (pin "2") (pinfunction "Ref_2") (pintype "passive"))
    )
    (net (code "88") (name "Net-(U5-IN+)") (class "Default")
      (node (ref "C38") (pin "1") (pinfunction "1_1") (pintype "passive"))
      (node (ref "R33") (pin "1") (pinfunction "1_1") (pintype "passive"))
      (node (ref "R34") (pin "1") (pinfunction "1_1") (pintype "passive"))
      (node (ref "U5") (pin "3") (pinfunction "IN+_3") (pintype "input"))
    )
    (net (code "89") (name "Net-(U5-IN-)") (class "Default")
      (node (ref "R35") (pin "2") (pinfunction "2_2") (pintype "passive"))
      (node (ref "U5") (pin "4") (pinfunction "IN-_4") (pintype "input"))
    )
    (net (code "90") (name "Net-(USB1-CC1)") (class "Default")
      (node (ref "R49") (pin "2") (pinfunction "2_2") (pintype "passive"))
      (node (ref "USB1") (pin "A5") (pinfunction "CC1_A5") (pintype "passive"))
    )
    (net (code "91") (name "Net-(USB1-CC2)") (class "Default")
      (node (ref "R50") (pin "1") (pinfunction "1_1") (pintype "passive"))
      (node (ref "USB1") (pin "B5") (pinfunction "CC2_B5") (pintype "passive"))
    )
    (net (code "92") (name "Net-(USB1-SH1)") (class "Default")
      (node (ref "C11") (pin "2") (pinfunction "2_2") (pintype "passive"))
      (node (ref "R5") (pin "2") (pinfunction "2_2") (pintype "passive"))
      (node (ref "USB1") (pin "1") (pinfunction "SH1_1") (pintype "passive"))
      (node (ref "USB1") (pin "2") (pinfunction "SH2_2") (pintype "passive"))
      (node (ref "USB1") (pin "3") (pinfunction "SH3_3") (pintype "passive"))
      (node (ref "USB1") (pin "4") (pinfunction "SH4_4") (pintype "passive"))
    )
    (net (code "93") (name "Net-(USB2-SH1)") (class "Default")
      (node (ref "C40") (pin "2") (pinfunction "2_2") (pintype "passive"))
      (node (ref "R36") (pin "2") (pinfunction "2_2") (pintype "passive"))
      (node (ref "USB2") (pin "1") (pinfunction "SH1_1") (pintype "passive"))
      (node (ref "USB2") (pin "2") (pinfunction "SH2_2") (pintype "passive"))
      (node (ref "USB2") (pin "3") (pinfunction "SH3_3") (pintype "passive"))
      (node (ref "USB2") (pin "4") (pinfunction "SH4_4") (pintype "passive"))
    )
    (net (code "94") (name "USBFS_VBUS") (class "Default")
      (node (ref "C16") (pin "1") (pinfunction "1_1") (pintype "passive"))
      (node (ref "D7") (pin "2") (pinfunction "2_2") (pintype "passive"))
      (node (ref "D9") (pin "1") (pinfunction "A_1") (pintype "passive"))
      (node (ref "P15") (pin "2") (pinfunction "2_2") (pintype "passive"))
      (node (ref "P5") (pin "1") (pinfunction "1_1") (pintype "passive"))
      (node (ref "Q1") (pin "3") (pinfunction "C_3") (pintype "passive"))
      (node (ref "R29") (pin "2") (pinfunction "2_2") (pintype "passive"))
      (node (ref "USB1") (pin "A4") (pinfunction "VBUS_A4") (pintype "passive"))
      (node (ref "USB1") (pin "A9") (pinfunction "VBUS_A9") (pintype "passive"))
      (node (ref "USB1") (pin "B4") (pinfunction "VBUS_B4") (pintype "passive"))
      (node (ref "USB1") (pin "B9") (pinfunction "VBUS_B9") (pintype "passive"))
    )
    (net (code "95") (name "USBPD_VBUS") (class "Default")
      (node (ref "C39") (pin "1") (pinfunction "1_1") (pintype "passive"))
      (node (ref "D10") (pin "2") (pinfunction "2_2") (pintype "passive"))
      (node (ref "D8") (pin "1") (pinfunction "A_1") (pintype "passive"))
      (node (ref "P1") (pin "1") (pinfunction "1_1") (pintype "passive"))
      (node (ref "P16") (pin "1") (pinfunction "1_1") (pintype "passive"))
      (node (ref "R33") (pin "2") (pinfunction "2_2") (pintype "passive"))
      (node (ref "USB2") (pin "A4") (pinfunction "VBUS_A4") (pintype "passive"))
      (node (ref "USB2") (pin "A9") (pinfunction "VBUS_A9") (pintype "passive"))
      (node (ref "USB2") (pin "B4") (pinfunction "VBUS_B4") (pintype "passive"))
      (node (ref "USB2") (pin "B9") (pinfunction "VBUS_B9") (pintype "passive"))
    )
    (net (code "96") (name "VBAT") (class "Default")
      (node (ref "C6") (pin "2") (pinfunction "2_2") (pintype "passive"))
      (node (ref "R27") (pin "2") (pinfunction "2_2") (pintype "passive"))
      (node (ref "SW1") (pin "3") (pinfunction "3_3") (pintype "passive"))
      (node (ref "SW1") (pin "4") (pinfunction "4_4") (pintype "passive"))
      (node (ref "U1") (pin "1") (pinfunction "VBAT_1") (pintype "power_in"))
      (node (ref "VD1") (pin "3") (pinfunction "3_3") (pintype "passive"))
    )
    (net (code "97") (name "VDD") (class "Default")
      (node (ref "C10") (pin "2") (pinfunction "2_2") (pintype "passive"))
      (node (ref "C13") (pin "2") (pinfunction "2_2") (pintype "passive"))
      (node (ref "C29") (pin "1") (pinfunction "1_1") (pintype "passive"))
      (node (ref "C7") (pin "2") (pinfunction "2_2") (pintype "passive"))
      (node (ref "C8") (pin "2") (pinfunction "2_2") (pintype "passive"))
      (node (ref "C9") (pin "2") (pinfunction "2_2") (pintype "passive"))
      (node (ref "D11") (pin "2") (pinfunction "2_2") (pintype "passive"))
      (node (ref "L2") (pin "1") (pintype "passive"))
      (node (ref "P11") (pin "1") (pinfunction "1_1") (pintype "passive"))
      (node (ref "P12") (pin "1") (pinfunction "1_1") (pintype "passive"))
      (node (ref "P2") (pin "11") (pinfunction "11_11") (pintype "passive"))
      (node (ref "P3") (pin "1") (pinfunction "1_1") (pintype "passive"))
      (node (ref "P4") (pin "11") (pinfunction "11_11") (pintype "passive"))
      (node (ref "P8") (pin "2") (pinfunction "2_2") (pintype "passive"))
      (node (ref "P9") (pin "2") (pinfunction "2_2") (pintype "passive"))
      (node (ref "R2") (pin "1") (pinfunction "1_1") (pintype "passive"))
      (node (ref "R26") (pin "1") (pinfunction "1_1") (pintype "passive"))
      (node (ref "R27") (pin "1") (pinfunction "1_1") (pintype "passive"))
      (node (ref "R8") (pin "1") (pinfunction "1_1") (pintype "passive"))
      (node (ref "SW3") (pin "3") (pinfunction "3_3") (pintype "passive"))
      (node (ref "SW3") (pin "4") (pinfunction "4_4") (pintype "passive"))
      (node (ref "U1") (pin "23") (pinfunction "VDD_23") (pintype "power_in"))
      (node (ref "U1") (pin "35") (pinfunction "VDD_35") (pintype "power_in"))
      (node (ref "U1") (pin "48") (pinfunction "VDD_48") (pintype "power_in"))
      (node (ref "U2") (pin "5") (pinfunction "VOUT_5") (pintype "passive"))
      (node (ref "VD1") (pin "1") (pinfunction "1_1") (pintype "passive"))
    )
    (net (code "98") (name "VREF") (class "Default")
      (node (ref "C2") (pin "2") (pinfunction "2_2") (pintype "passive"))
      (node (ref "C35") (pin "1") (pinfunction "1_1") (pintype "passive"))
      (node (ref "C36") (pin "1") (pinfunction "1_1") (pintype "passive"))
      (node (ref "L1") (pin "1") (pintype "passive"))
      (node (ref "P2") (pin "8") (pinfunction "8_8") (pintype "passive"))
      (node (ref "P4") (pin "8") (pinfunction "8_8") (pintype "passive"))
      (node (ref "Q1") (pin "2") (pinfunction "E_2") (pintype "passive"))
      (node (ref "R26") (pin "2") (pinfunction "2_2") (pintype "passive"))
      (node (ref "R30") (pin "2") (pinfunction "2_2") (pintype "passive"))
      (node (ref "R31") (pin "2") (pinfunction "2_2") (pintype "passive"))
    )
    (net (code "99") (name "VREFP") (class "Default")
      (node (ref "C1") (pin "1") (pinfunction "1_1") (pintype "passive"))
      (node (ref "C5") (pin "1") (pinfunction "1_1") (pintype "passive"))
      (node (ref "L1") (pin "2") (pinfunction "2_2") (pintype "passive"))
      (node (ref "U1") (pin "20") (pinfunction "VREF+_20") (pintype "power_in"))
    )
    (net (code "100") (name "unconnected-(H1-Pad1)") (class "Default")
      (node (ref "H1") (pin "1") (pinfunction "1_1") (pintype "passive"))
    )
    (net (code "101") (name "unconnected-(H2-Pad1)") (class "Default")
      (node (ref "H2") (pin "1") (pinfunction "1_1") (pintype "passive"))
    )
    (net (code "102") (name "unconnected-(H3-Pad1)") (class "Default")
      (node (ref "H3") (pin "1") (pinfunction "1_1") (pintype "passive"))
    )
    (net (code "103") (name "unconnected-(H4-Pad1)") (class "Default")
      (node (ref "H4") (pin "1") (pinfunction "1_1") (pintype "passive"))
    )
    (net (code "104") (name "unconnected-(USB1-SBU1-PadA8)") (class "Default")
      (node (ref "USB1") (pin "A8") (pinfunction "SBU1_A8") (pintype "passive+no_connect"))
    )
    (net (code "105") (name "unconnected-(USB1-SBU2-PadB8)") (class "Default")
      (node (ref "USB1") (pin "B8") (pinfunction "SBU2_B8") (pintype "passive+no_connect"))
    )
    (net (code "106") (name "unconnected-(USB2-D+-PadA6)") (class "Default")
      (node (ref "USB2") (pin "A6") (pinfunction "D+_A6") (pintype "passive+no_connect"))
    )
    (net (code "107") (name "unconnected-(USB2-D+-PadB6)") (class "Default")
      (node (ref "USB2") (pin "B6") (pinfunction "D+_B6") (pintype "passive+no_connect"))
    )
    (net (code "108") (name "unconnected-(USB2-D--PadA7)") (class "Default")
      (node (ref "USB2") (pin "A7") (pinfunction "D-_A7") (pintype "passive+no_connect"))
    )
    (net (code "109") (name "unconnected-(USB2-D--PadB7)") (class "Default")
      (node (ref "USB2") (pin "B7") (pinfunction "D-_B7") (pintype "passive+no_connect"))
    )
    (net (code "110") (name "unconnected-(USB2-SBU1-PadA8)") (class "Default")
      (node (ref "USB2") (pin "A8") (pinfunction "SBU1_A8") (pintype "passive+no_connect"))
    )
    (net (code "111") (name "unconnected-(USB2-SBU2-PadB8)") (class "Default")
      (node (ref "USB2") (pin "B8") (pinfunction "SBU2_B8") (pintype "passive+no_connect"))
    )
    (net (code "112") (name "unconnected-(VD2-VBUS-Pad5)") (class "Default")
      (node (ref "VD2") (pin "5") (pinfunction "VBUS_5") (pintype "passive+no_connect"))
    )
  )
)
